# navx_micro_4_1.net
KiCad netlist of a schematic drawn in EAGLE
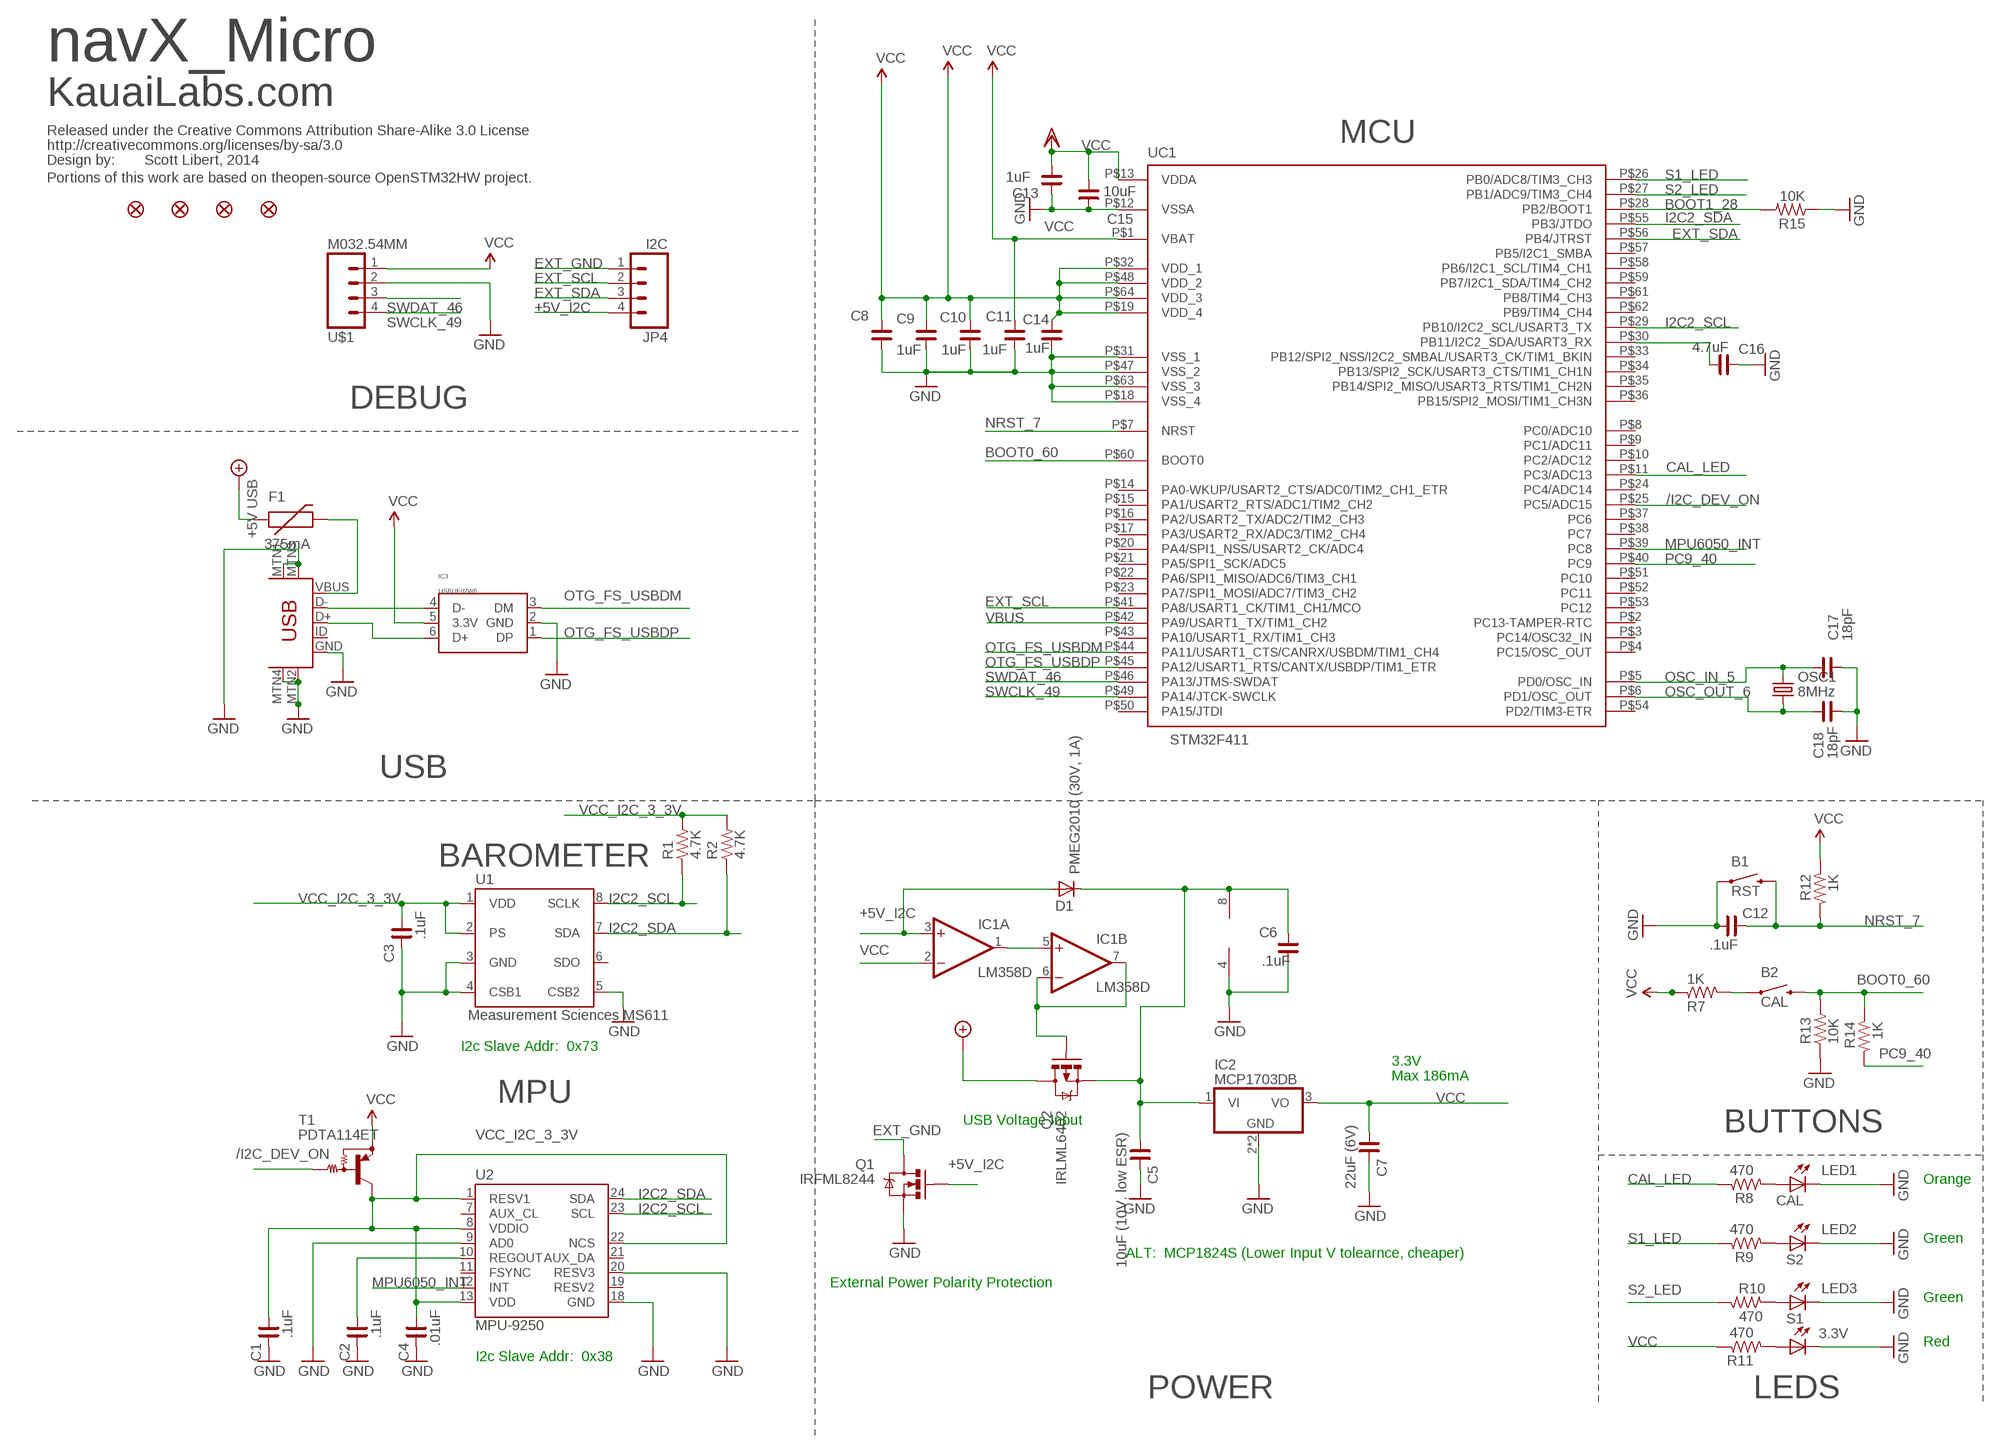
[diagram p0: schematic, sheet 1]

(export (version "E")
  (design (tool "Eeschema 10.0.6"))
  (components
    (comp (ref "B1")
      (value "RST")
      (footprint "eagle-import:TACTILE-SWITCH-1101NE")
      (libsource (lib "eagle-import") (part "SWITCH-MOMENTARY-2-SMD-1101NE"))
    )
    (comp (ref "B2")
      (value "CAL")
      (footprint "eagle-import:TACTILE-SWITCH-1101NE")
      (libsource (lib "eagle-import") (part "SWITCH-MOMENTARY-2-SMD-1101NE"))
    )
    (comp (ref "C1")
      (value ".1uF")
      (footprint "eagle-import:C0603")
      (libsource (lib "eagle-import") (part "C_0603"))
    )
    (comp (ref "C2")
      (value ".1uF")
      (footprint "eagle-import:C0603")
      (libsource (lib "eagle-import") (part "C_0603"))
    )
    (comp (ref "C3")
      (value ".1uF")
      (footprint "eagle-import:C0603")
      (fields (field (name "DIGIKEY_PART_NUMBER") "399-1096-1-ND"))
      (libsource (lib "eagle-import") (part "C_0603"))
    )
    (comp (ref "C4")
      (value ".01uF")
      (footprint "eagle-import:C0603")
      (libsource (lib "eagle-import") (part "C_0603"))
    )
    (comp (ref "C5")
      (value "10uF (10V. low ESR)")
      (footprint "eagle-import:C0805")
      (fields (field (name "DIGIKEY_PART_NUMBER") "399-1158-1-ND"))
      (libsource (lib "eagle-import") (part "C_0805"))
    )
    (comp (ref "C6")
      (value ".1uF")
      (footprint "eagle-import:C0603")
      (libsource (lib "eagle-import") (part "C_0603"))
    )
    (comp (ref "C7")
      (value "22uF (6V)")
      (footprint "eagle-import:C0805")
      (fields (field (name "DIGIKEY_PART_NUMBER") "399-1158-1-ND"))
      (libsource (lib "eagle-import") (part "C_0805"))
    )
    (comp (ref "C8")
      (value "1uF")
      (footprint "eagle-import:C0603")
      (fields (field (name "DIGIKEY_PART_NUMBER") "399-3118-1-ND"))
      (libsource (lib "eagle-import") (part "C_0603"))
    )
    (comp (ref "C9")
      (value "1uF")
      (footprint "eagle-import:C0603")
      (libsource (lib "eagle-import") (part "C_0603"))
    )
    (comp (ref "C10")
      (value "1uF")
      (footprint "eagle-import:C0603")
      (libsource (lib "eagle-import") (part "C_0603"))
    )
    (comp (ref "C11")
      (value "1uF")
      (footprint "eagle-import:C0603")
      (libsource (lib "eagle-import") (part "C_0603"))
    )
    (comp (ref "C12")
      (value ".1uF")
      (footprint "eagle-import:C0603")
      (libsource (lib "eagle-import") (part "C_0603"))
    )
    (comp (ref "C13")
      (value "1uF")
      (footprint "eagle-import:C0603")
      (libsource (lib "eagle-import") (part "C_0603"))
    )
    (comp (ref "C14")
      (value "1uF")
      (footprint "eagle-import:C0603")
      (libsource (lib "eagle-import") (part "C_0603"))
    )
    (comp (ref "C15")
      (value "10uF")
      (footprint "eagle-import:C0805")
      (libsource (lib "eagle-import") (part "C_0805"))
    )
    (comp (ref "C16")
      (value "4.7uF")
      (footprint "eagle-import:C0603")
      (libsource (lib "eagle-import") (part "C_0603"))
    )
    (comp (ref "C17")
      (value "18pF")
      (footprint "eagle-import:C0603")
      (libsource (lib "eagle-import") (part "C_0603"))
    )
    (comp (ref "C18")
      (value "18pF")
      (footprint "eagle-import:C0603")
      (libsource (lib "eagle-import") (part "C_0603"))
    )
    (comp (ref "D1")
      (value "PMEG2010 (30V, 1A)")
      (footprint "eagle-import:SOD-323")
      (libsource (lib "eagle-import") (part "DIODESOD-323"))
    )
    (comp (ref "F1")
      (value "375mA")
      (footprint "eagle-import:0603")
      (libsource (lib "eagle-import") (part "PTC0603"))
    )
    (comp (ref "IC1")
      (value "LM358D")
      (footprint "eagle-import:SO08")
      (libsource (lib "eagle-import") (part "LM358D"))
    )
    (comp (ref "IC2")
      (value "MCP1703DB")
      (footprint "eagle-import:MCP1703DB")
      (fields (field (name "DIGIKEY_PART_NUMBER") "MCP1703T-3302E/DBCT-ND"))
      (libsource (lib "eagle-import") (part "MCP1703DB"))
    )
    (comp (ref "IC3")
      (value "USBUF02W6")
      (footprint "eagle-import:SC70-6")
      (fields (field (name "DIGIKEY_PART_NUMBER") "497-3743-1-ND"))
      (libsource (lib "eagle-import") (part "USBUF02W6"))
    )
    (comp (ref "JP4")
      (value "I2C")
      (footprint "eagle-import:1X04")
      (libsource (lib "eagle-import") (part "M04PTH"))
    )
    (comp (ref "JP21")
      (value "FIDUCIAL1X2")
      (footprint "eagle-import:FIDUCIAL-1X2")
      (libsource (lib "eagle-import") (part "FIDUCIAL1X2"))
    )
    (comp (ref "JP22")
      (value "FIDUCIAL1X2")
      (footprint "eagle-import:FIDUCIAL-1X2")
      (libsource (lib "eagle-import") (part "FIDUCIAL1X2"))
    )
    (comp (ref "JP23")
      (value "FIDUCIAL1X2")
      (footprint "eagle-import:FIDUCIAL-1X2")
      (libsource (lib "eagle-import") (part "FIDUCIAL1X2"))
    )
    (comp (ref "JP24")
      (value "FIDUCIAL1X2")
      (footprint "eagle-import:FIDUCIAL-1X2")
      (libsource (lib "eagle-import") (part "FIDUCIAL1X2"))
    )
    (comp (ref "LED1")
      (value "CAL")
      (footprint "eagle-import:CHIP-LED0603")
      (libsource (lib "eagle-import") (part "LEDCHIP-LED0603"))
    )
    (comp (ref "LED2")
      (value "S2")
      (footprint "eagle-import:CHIP-LED0603")
      (libsource (lib "eagle-import") (part "LEDCHIP-LED0603"))
    )
    (comp (ref "LED3")
      (value "S1")
      (footprint "eagle-import:CHIP-LED0603")
      (libsource (lib "eagle-import") (part "LEDCHIP-LED0603"))
    )
    (comp (ref "LED4")
      (value "3.3V")
      (footprint "eagle-import:CHIP-LED0603")
      (libsource (lib "eagle-import") (part "LEDCHIP-LED0603"))
    )
    (comp (ref "LICENSE_TEXT")
      (value "CREATIVE_COMMONS")
      (footprint "eagle-import:CREATIVE_COMMONS")
      (libsource (lib "eagle-import") (part "CREATIVE_COMMONS"))
    )
    (comp (ref "OSC1")
      (value "8MHz")
      (footprint "eagle-import:CRYSTAL-SMD-5X3")
      (libsource (lib "eagle-import") (part "CRYSTAL5X3"))
    )
    (comp (ref "Q1")
      (value "IRFML8244")
      (footprint "eagle-import:SOT23")
      (fields (field (name "DIGIKEY_PART_NUMBER") "DMN3404LDICT-ND"))
      (libsource (lib "eagle-import") (part "MOSFET-NCHANNELBSS123LT1G"))
    )
    (comp (ref "Q2")
      (value "IRLML6402")
      (footprint "eagle-import:SOT23-3")
      (libsource (lib "eagle-import") (part "MOSFET-PCHANNELSMD"))
    )
    (comp (ref "R1")
      (value "4.7K")
      (footprint "eagle-import:R0603")
      (libsource (lib "eagle-import") (part "R_0603"))
    )
    (comp (ref "R2")
      (value "4.7K")
      (footprint "eagle-import:R0603")
      (libsource (lib "eagle-import") (part "R_0603"))
    )
    (comp (ref "R7")
      (value "1K")
      (footprint "eagle-import:R0603")
      (libsource (lib "eagle-import") (part "R_0603"))
    )
    (comp (ref "R8")
      (value "470")
      (footprint "eagle-import:R0603")
      (libsource (lib "eagle-import") (part "R_0603"))
    )
    (comp (ref "R9")
      (value "470")
      (footprint "eagle-import:R0603")
      (libsource (lib "eagle-import") (part "R_0603"))
    )
    (comp (ref "R10")
      (value "470")
      (footprint "eagle-import:R0603")
      (libsource (lib "eagle-import") (part "R_0603"))
    )
    (comp (ref "R11")
      (value "470")
      (footprint "eagle-import:R0603")
      (libsource (lib "eagle-import") (part "R_0603"))
    )
    (comp (ref "R12")
      (value "1K")
      (footprint "eagle-import:R0603")
      (libsource (lib "eagle-import") (part "R_0603"))
    )
    (comp (ref "R13")
      (value "10K")
      (footprint "eagle-import:R0603")
      (libsource (lib "eagle-import") (part "R_0603"))
    )
    (comp (ref "R14")
      (value "1K")
      (footprint "eagle-import:R0603")
      (libsource (lib "eagle-import") (part "R_0603"))
    )
    (comp (ref "R15")
      (value "10K")
      (footprint "eagle-import:R0603")
      (libsource (lib "eagle-import") (part "R_0603"))
    )
    (comp (ref "T1")
      (value "PDTA114ET")
      (footprint "eagle-import:SOT23-3")
      (libsource (lib "eagle-import") (part "PNP-DRIVERSOT23-3"))
    )
    (comp (ref "U$1")
      (value "M032.54MM")
      (footprint "eagle-import:1X04_NO_SILK")
      (libsource (lib "eagle-import") (part "M041X04_NO_SILK"))
    )
    (comp (ref "U1")
      (value "Measurement Sciences MS611")
      (footprint "eagle-import:MS5611")
      (fields (field (name "DIGIKEY_PART_NUMBER") "MPL115A2-ND"))
      (libsource (lib "eagle-import") (part "MS5611"))
    )
    (comp (ref "U2")
      (value "MPU-9250")
      (footprint "eagle-import:QFN24_3MM_INVENSENSE")
      (fields
        (field (name "DIGIKEY_PART_NUMBER") "1428-1019-1-ND")
        (field (name "MANUFACTURER") "INVENSENSE")
      )
      (libsource (lib "eagle-import") (part "MPU-9250"))
    )
    (comp (ref "UC1")
      (value "STM32F411")
      (footprint "eagle-import:TQFP-10X10-64")
      (fields (field (name "DIGIKEY_PART_NUMBER") "497-11154-ND"))
      (libsource (lib "eagle-import") (part "STM32F103"))
    )
    (comp (ref "USB")
      (value "Mini-USB")
      (footprint "eagle-import:USB-MINIB")
      (fields (field (name "DIGIKEY_PART_NUMBER") "151-1206-1-ND"))
      (libsource (lib "eagle-import") (part "USB-MINIB-5PIN"))
    )
  )
  (nets
    (net (code "1") (name "+5V USB") (class "Default")
      (node (ref "F1") (pin "1") (pinfunction "1_1") (pintype "bidirectional"))
      (node (ref "Q2") (pin "3") (pinfunction "D_3") (pintype "passive"))
    )
    (net (code "2") (name "/+5V_I2C") (class "Default")
      (node (ref "D1") (pin "A") (pinfunction "A_A") (pintype "passive"))
      (node (ref "IC1") (pin "3") (pinfunction "+IN_3") (pintype "input"))
      (node (ref "JP4") (pin "4") (pinfunction "4_4") (pintype "passive"))
      (node (ref "Q1") (pin "1") (pinfunction "G_1") (pintype "passive"))
    )
    (net (code "3") (name "/BOOT0_60") (class "Default")
      (node (ref "B2") (pin "P$2") (pinfunction "2_P$2") (pintype "passive"))
      (node (ref "R13") (pin "2") (pinfunction "2_2") (pintype "passive"))
      (node (ref "R14") (pin "1") (pinfunction "1_1") (pintype "passive"))
      (node (ref "UC1") (pin "P$60") (pinfunction "BOOT0_P$60") (pintype "bidirectional"))
    )
    (net (code "4") (name "/BOOT1_28") (class "Default")
      (node (ref "R15") (pin "2") (pinfunction "2_2") (pintype "passive"))
      (node (ref "UC1") (pin "P$28") (pinfunction "PB2/BOOT1_P$28") (pintype "bidirectional"))
    )
    (net (code "5") (name "/CAL_LED") (class "Default")
      (node (ref "R8") (pin "1") (pinfunction "1_1") (pintype "passive"))
      (node (ref "UC1") (pin "P$11") (pinfunction "PC3/ADC13_P$11") (pintype "bidirectional"))
    )
    (net (code "6") (name "/EXT_GND") (class "Default")
      (node (ref "JP4") (pin "1") (pinfunction "1_1") (pintype "passive"))
      (node (ref "Q1") (pin "3") (pinfunction "D_3") (pintype "passive"))
    )
    (net (code "7") (name "/EXT_SCL") (class "Default")
      (node (ref "JP4") (pin "2") (pinfunction "2_2") (pintype "passive"))
      (node (ref "UC1") (pin "P$41") (pinfunction "PA8/USART1_CK/TIM1_CH1/MCO_P$41") (pintype "bidirectional"))
    )
    (net (code "8") (name "/EXT_SDA") (class "Default")
      (node (ref "JP4") (pin "3") (pinfunction "3_3") (pintype "passive"))
      (node (ref "UC1") (pin "P$56") (pinfunction "PB4/JTRST_P$56") (pintype "bidirectional"))
    )
    (net (code "9") (name "/I2C2_SCL") (class "Default")
      (node (ref "R1") (pin "1") (pinfunction "1_1") (pintype "passive"))
      (node (ref "U1") (pin "8") (pinfunction "SCLK_8") (pintype "bidirectional"))
      (node (ref "U2") (pin "23") (pinfunction "SCL_23") (pintype "bidirectional"))
      (node (ref "UC1") (pin "P$29") (pinfunction "PB10/I2C2_SCL/USART3_TX_P$29") (pintype "bidirectional"))
    )
    (net (code "10") (name "/I2C2_SDA") (class "Default")
      (node (ref "R2") (pin "1") (pinfunction "1_1") (pintype "passive"))
      (node (ref "U1") (pin "7") (pinfunction "SDA_7") (pintype "bidirectional"))
      (node (ref "U2") (pin "24") (pinfunction "SDA_24") (pintype "bidirectional"))
      (node (ref "UC1") (pin "P$55") (pinfunction "PB3/JTDO_P$55") (pintype "bidirectional"))
    )
    (net (code "11") (name "/MPU6050_INT") (class "Default")
      (node (ref "U2") (pin "12") (pinfunction "INT_12") (pintype "bidirectional"))
      (node (ref "UC1") (pin "P$39") (pinfunction "PC8_P$39") (pintype "bidirectional"))
    )
    (net (code "12") (name "/NRST_7") (class "Default")
      (node (ref "B1") (pin "P$2") (pinfunction "2_P$2") (pintype "passive"))
      (node (ref "C12") (pin "2") (pinfunction "2_2") (pintype "passive"))
      (node (ref "R12") (pin "2") (pinfunction "2_2") (pintype "passive"))
      (node (ref "UC1") (pin "P$7") (pinfunction "NRST_P$7") (pintype "bidirectional"))
    )
    (net (code "13") (name "/OSC_IN_5") (class "Default")
      (node (ref "C17") (pin "2") (pinfunction "2_2") (pintype "passive"))
      (node (ref "OSC1") (pin "3") (pinfunction "2_3") (pintype "passive"))
      (node (ref "UC1") (pin "P$5") (pinfunction "PD0/OSC_IN_P$5") (pintype "bidirectional"))
    )
    (net (code "14") (name "/OSC_OUT_6") (class "Default")
      (node (ref "C18") (pin "2") (pinfunction "2_2") (pintype "passive"))
      (node (ref "OSC1") (pin "1") (pinfunction "1_1") (pintype "passive"))
      (node (ref "UC1") (pin "P$6") (pinfunction "PD1/OSC_OUT_P$6") (pintype "bidirectional"))
    )
    (net (code "15") (name "/OTG_FS_USBDM") (class "Default")
      (node (ref "IC3") (pin "3") (pinfunction "DM_3") (pintype "bidirectional"))
      (node (ref "UC1") (pin "P$44") (pinfunction "PA11/USART1_CTS/CANRX/USBDM/TIM1_CH4_P$44") (pintype "bidirectional"))
    )
    (net (code "16") (name "/OTG_FS_USBDP") (class "Default")
      (node (ref "IC3") (pin "1") (pinfunction "DP_1") (pintype "bidirectional"))
      (node (ref "UC1") (pin "P$45") (pinfunction "PA12/USART1_RTS/CANTX/USBDP/TIM1_ETR_P$45") (pintype "bidirectional"))
    )
    (net (code "17") (name "/PC9_40") (class "Default")
      (node (ref "R14") (pin "2") (pinfunction "2_2") (pintype "passive"))
      (node (ref "UC1") (pin "P$40") (pinfunction "PC9_P$40") (pintype "bidirectional"))
    )
    (net (code "18") (name "/S1_LED") (class "Default")
      (node (ref "R9") (pin "1") (pinfunction "1_1") (pintype "passive"))
      (node (ref "UC1") (pin "P$26") (pinfunction "PB0/ADC8/TIM3_CH3_P$26") (pintype "bidirectional"))
    )
    (net (code "19") (name "/S2_LED") (class "Default")
      (node (ref "R10") (pin "2") (pinfunction "2_2") (pintype "passive"))
      (node (ref "UC1") (pin "P$27") (pinfunction "PB1/ADC9/TIM3_CH4_P$27") (pintype "bidirectional"))
    )
    (net (code "20") (name "/SWCLK_49") (class "Default")
      (node (ref "U$1") (pin "4") (pinfunction "4_4") (pintype "passive"))
      (node (ref "UC1") (pin "P$49") (pinfunction "PA14/JTCK-SWCLK_P$49") (pintype "bidirectional"))
    )
    (net (code "21") (name "/SWDAT_46") (class "Default")
      (node (ref "U$1") (pin "3") (pinfunction "3_3") (pintype "passive"))
      (node (ref "UC1") (pin "P$46") (pinfunction "PA13/JTMS-SWDAT_P$46") (pintype "bidirectional"))
    )
    (net (code "22") (name "/VBUS") (class "Default")
      (node (ref "F1") (pin "2") (pinfunction "2_2") (pintype "bidirectional"))
      (node (ref "UC1") (pin "P$42") (pinfunction "PA9/USART1_TX/TIM1_CH2_P$42") (pintype "bidirectional"))
      (node (ref "USB") (pin "VBUS") (pinfunction "VBUS_VBUS") (pintype "bidirectional"))
    )
    (net (code "23") (name "/VCC_I2C_3_3V") (class "Default")
      (node (ref "C1") (pin "1") (pinfunction "1_1") (pintype "passive"))
      (node (ref "C3") (pin "1") (pinfunction "1_1") (pintype "passive"))
      (node (ref "C4") (pin "1") (pinfunction "1_1") (pintype "passive"))
      (node (ref "R1") (pin "2") (pinfunction "2_2") (pintype "passive"))
      (node (ref "R2") (pin "2") (pinfunction "2_2") (pintype "passive"))
      (node (ref "T1") (pin "3") (pinfunction "C_3") (pintype "passive"))
      (node (ref "U1") (pin "1") (pinfunction "VDD_1") (pintype "bidirectional"))
      (node (ref "U1") (pin "2") (pinfunction "PS_2") (pintype "bidirectional"))
      (node (ref "U2") (pin "1") (pinfunction "RESV1_1") (pintype "bidirectional"))
      (node (ref "U2") (pin "13") (pinfunction "VDD_13") (pintype "bidirectional"))
      (node (ref "U2") (pin "22") (pinfunction "NCS_22") (pintype "bidirectional"))
      (node (ref "U2") (pin "8") (pinfunction "VDDIO_8") (pintype "bidirectional"))
    )
    (net (code "24") (name "/{slash}I2C_DEV_ON") (class "Default")
      (node (ref "T1") (pin "1") (pinfunction "B_1") (pintype "passive"))
      (node (ref "UC1") (pin "P$25") (pinfunction "PC5/ADC15_P$25") (pintype "bidirectional"))
    )
    (net (code "25") (name "GND") (class "Default")
      (node (ref "B1") (pin "P$1") (pinfunction "1_P$1") (pintype "passive"))
      (node (ref "C1") (pin "2") (pinfunction "2_2") (pintype "passive"))
      (node (ref "C10") (pin "1") (pinfunction "1_1") (pintype "passive"))
      (node (ref "C11") (pin "1") (pinfunction "1_1") (pintype "passive"))
      (node (ref "C12") (pin "1") (pinfunction "1_1") (pintype "passive"))
      (node (ref "C13") (pin "1") (pinfunction "1_1") (pintype "passive"))
      (node (ref "C14") (pin "1") (pinfunction "1_1") (pintype "passive"))
      (node (ref "C15") (pin "2") (pinfunction "2_2") (pintype "passive"))
      (node (ref "C16") (pin "1") (pinfunction "1_1") (pintype "passive"))
      (node (ref "C17") (pin "1") (pinfunction "1_1") (pintype "passive"))
      (node (ref "C18") (pin "1") (pinfunction "1_1") (pintype "passive"))
      (node (ref "C2") (pin "2") (pinfunction "2_2") (pintype "passive"))
      (node (ref "C3") (pin "2") (pinfunction "2_2") (pintype "passive"))
      (node (ref "C4") (pin "2") (pinfunction "2_2") (pintype "passive"))
      (node (ref "C5") (pin "2") (pinfunction "2_2") (pintype "passive"))
      (node (ref "C6") (pin "1") (pinfunction "1_1") (pintype "passive"))
      (node (ref "C7") (pin "2") (pinfunction "2_2") (pintype "passive"))
      (node (ref "C8") (pin "1") (pinfunction "1_1") (pintype "passive"))
      (node (ref "C9") (pin "1") (pinfunction "1_1") (pintype "passive"))
      (node (ref "IC1") (pin "4") (pinfunction "V-_4") (pintype "power_in"))
      (node (ref "IC2") (pin "2") (pinfunction "GND_2") (pintype "passive"))
      (node (ref "IC2") (pin "4") (pinfunction "GND_4") (pintype "passive"))
      (node (ref "IC3") (pin "2") (pinfunction "GND_2") (pintype "bidirectional"))
      (node (ref "LED1") (pin "C") (pinfunction "C_C") (pintype "passive"))
      (node (ref "LED2") (pin "C") (pinfunction "C_C") (pintype "passive"))
      (node (ref "LED3") (pin "C") (pinfunction "C_C") (pintype "passive"))
      (node (ref "LED4") (pin "C") (pinfunction "C_C") (pintype "passive"))
      (node (ref "Q1") (pin "2") (pinfunction "S_2") (pintype "passive"))
      (node (ref "R13") (pin "1") (pinfunction "1_1") (pintype "passive"))
      (node (ref "R15") (pin "1") (pinfunction "1_1") (pintype "passive"))
      (node (ref "U$1") (pin "2") (pinfunction "2_2") (pintype "passive"))
      (node (ref "U1") (pin "3") (pinfunction "GND_3") (pintype "bidirectional"))
      (node (ref "U1") (pin "4") (pinfunction "CSB1_4") (pintype "bidirectional"))
      (node (ref "U1") (pin "5") (pinfunction "CSB2_5") (pintype "bidirectional"))
      (node (ref "U2") (pin "18") (pinfunction "GND_18") (pintype "bidirectional"))
      (node (ref "U2") (pin "20") (pinfunction "RESV3_20") (pintype "bidirectional"))
      (node (ref "U2") (pin "9") (pinfunction "AD0_9") (pintype "bidirectional"))
      (node (ref "UC1") (pin "P$12") (pinfunction "VSSA_P$12") (pintype "power_in"))
      (node (ref "UC1") (pin "P$18") (pinfunction "VSS_4_P$18") (pintype "power_in"))
      (node (ref "UC1") (pin "P$31") (pinfunction "VSS_1_P$31") (pintype "power_in"))
      (node (ref "UC1") (pin "P$47") (pinfunction "VSS_2_P$47") (pintype "power_in"))
      (node (ref "UC1") (pin "P$63") (pinfunction "VSS_3_P$63") (pintype "power_in"))
      (node (ref "USB") (pin "GND") (pinfunction "GND_GND") (pintype "bidirectional"))
      (node (ref "USB") (pin "MTN1") (pinfunction "MTN2_MTN1") (pintype "bidirectional"))
      (node (ref "USB") (pin "MTN2") (pinfunction "MTN3_MTN2") (pintype "bidirectional"))
      (node (ref "USB") (pin "MTN3") (pinfunction "MTN1_MTN3") (pintype "bidirectional"))
      (node (ref "USB") (pin "MTN4") (pinfunction "MTN4_MTN4") (pintype "bidirectional"))
    )
    (net (code "26") (name "Net-(B2-1)") (class "Default")
      (node (ref "B2") (pin "P$1") (pinfunction "1_P$1") (pintype "passive"))
      (node (ref "R7") (pin "2") (pinfunction "2_2") (pintype "passive"))
    )
    (net (code "27") (name "Net-(IC1A-OUT)") (class "Default")
      (node (ref "IC1") (pin "1") (pinfunction "OUT_1") (pintype "output"))
      (node (ref "IC1") (pin "5") (pinfunction "+IN_5") (pintype "input"))
    )
    (net (code "28") (name "Net-(IC1B--IN)") (class "Default")
      (node (ref "IC1") (pin "6") (pinfunction "-IN_6") (pintype "input"))
      (node (ref "IC1") (pin "7") (pinfunction "OUT_7") (pintype "output"))
      (node (ref "Q2") (pin "1") (pinfunction "G_1") (pintype "passive"))
    )
    (net (code "29") (name "Net-(IC1C-V+)") (class "Default")
      (node (ref "C5") (pin "1") (pinfunction "1_1") (pintype "passive"))
      (node (ref "C6") (pin "2") (pinfunction "2_2") (pintype "passive"))
      (node (ref "D1") (pin "C") (pinfunction "C_C") (pintype "passive"))
      (node (ref "IC1") (pin "8") (pinfunction "V+_8") (pintype "power_in"))
      (node (ref "IC2") (pin "1") (pinfunction "VI_1") (pintype "input"))
      (node (ref "Q2") (pin "2") (pinfunction "S_2") (pintype "passive"))
    )
    (net (code "30") (name "Net-(IC3-D+)") (class "Default")
      (node (ref "IC3") (pin "6") (pinfunction "D+_6") (pintype "bidirectional"))
      (node (ref "USB") (pin "D+") (pinfunction "D+_D+") (pintype "bidirectional"))
    )
    (net (code "31") (name "Net-(IC3-D-)") (class "Default")
      (node (ref "IC3") (pin "4") (pinfunction "D-_4") (pintype "bidirectional"))
      (node (ref "USB") (pin "D-") (pinfunction "D-_D-") (pintype "bidirectional"))
    )
    (net (code "32") (name "Net-(LED1-PadA)") (class "Default")
      (node (ref "LED1") (pin "A") (pinfunction "A_A") (pintype "passive"))
      (node (ref "R8") (pin "2") (pinfunction "2_2") (pintype "passive"))
    )
    (net (code "33") (name "Net-(LED2-PadA)") (class "Default")
      (node (ref "LED2") (pin "A") (pinfunction "A_A") (pintype "passive"))
      (node (ref "R9") (pin "2") (pinfunction "2_2") (pintype "passive"))
    )
    (net (code "34") (name "Net-(LED3-PadA)") (class "Default")
      (node (ref "LED3") (pin "A") (pinfunction "A_A") (pintype "passive"))
      (node (ref "R10") (pin "1") (pinfunction "1_1") (pintype "passive"))
    )
    (net (code "35") (name "Net-(LED4-PadA)") (class "Default")
      (node (ref "LED4") (pin "A") (pinfunction "A_A") (pintype "passive"))
      (node (ref "R11") (pin "2") (pinfunction "2_2") (pintype "passive"))
    )
    (net (code "36") (name "Net-(U2-REGOUT)") (class "Default")
      (node (ref "C2") (pin "1") (pinfunction "1_1") (pintype "passive"))
      (node (ref "U2") (pin "10") (pinfunction "REGOUT_10") (pintype "bidirectional"))
    )
    (net (code "37") (name "Net-(UC1-PB11{slash}I2C2_SDA{slash}USART3_RX)") (class "Default")
      (node (ref "C16") (pin "2") (pinfunction "2_2") (pintype "passive"))
      (node (ref "UC1") (pin "P$30") (pinfunction "PB11/I2C2_SDA/USART3_RX_P$30") (pintype "bidirectional"))
    )
    (net (code "38") (name "VCC") (class "Default")
      (node (ref "C10") (pin "2") (pinfunction "2_2") (pintype "passive"))
      (node (ref "C11") (pin "2") (pinfunction "2_2") (pintype "passive"))
      (node (ref "C13") (pin "2") (pinfunction "2_2") (pintype "passive"))
      (node (ref "C14") (pin "2") (pinfunction "2_2") (pintype "passive"))
      (node (ref "C15") (pin "1") (pinfunction "1_1") (pintype "passive"))
      (node (ref "C7") (pin "1") (pinfunction "1_1") (pintype "passive"))
      (node (ref "C8") (pin "2") (pinfunction "2_2") (pintype "passive"))
      (node (ref "C9") (pin "2") (pinfunction "2_2") (pintype "passive"))
      (node (ref "IC1") (pin "2") (pinfunction "-IN_2") (pintype "input"))
      (node (ref "IC2") (pin "3") (pinfunction "VO_3") (pintype "passive"))
      (node (ref "IC3") (pin "5") (pinfunction "3.3V_5") (pintype "bidirectional"))
      (node (ref "R11") (pin "1") (pinfunction "1_1") (pintype "passive"))
      (node (ref "R12") (pin "1") (pinfunction "1_1") (pintype "passive"))
      (node (ref "R7") (pin "1") (pinfunction "1_1") (pintype "passive"))
      (node (ref "T1") (pin "2") (pinfunction "E_2") (pintype "passive"))
      (node (ref "U$1") (pin "1") (pinfunction "1_1") (pintype "passive"))
      (node (ref "UC1") (pin "P$1") (pinfunction "VBAT_P$1") (pintype "power_in"))
      (node (ref "UC1") (pin "P$13") (pinfunction "VDDA_P$13") (pintype "power_in"))
      (node (ref "UC1") (pin "P$19") (pinfunction "VDD_4_P$19") (pintype "power_in"))
      (node (ref "UC1") (pin "P$32") (pinfunction "VDD_1_P$32") (pintype "power_in"))
      (node (ref "UC1") (pin "P$48") (pinfunction "VDD_2_P$48") (pintype "power_in"))
      (node (ref "UC1") (pin "P$64") (pinfunction "VDD_3_P$64") (pintype "power_in"))
    )
    (net (code "39") (name "unconnected-(U1-SDO-Pad6)") (class "Default")
      (node (ref "U1") (pin "6") (pinfunction "SDO_6") (pintype "bidirectional"))
    )
    (net (code "40") (name "unconnected-(U2-AUX_CL-Pad7)") (class "Default")
      (node (ref "U2") (pin "7") (pinfunction "AUX_CL_7") (pintype "bidirectional"))
    )
    (net (code "41") (name "unconnected-(U2-AUX_DA-Pad21)") (class "Default")
      (node (ref "U2") (pin "21") (pinfunction "AUX_DA_21") (pintype "bidirectional"))
    )
    (net (code "42") (name "unconnected-(U2-FSYNC-Pad11)") (class "Default")
      (node (ref "U2") (pin "11") (pinfunction "FSYNC_11") (pintype "bidirectional"))
    )
    (net (code "43") (name "unconnected-(U2-RESV2-Pad19)") (class "Default")
      (node (ref "U2") (pin "19") (pinfunction "RESV2_19") (pintype "bidirectional"))
    )
    (net (code "44") (name "unconnected-(UC1-PA0-WKUP{slash}USART2_CTS{slash}ADC0{slash}TIM2_CH1_ETR-PadP$14)") (class "Default")
      (node (ref "UC1") (pin "P$14") (pinfunction "PA0-WKUP/USART2_CTS/ADC0/TIM2_CH1_ETR_P$14") (pintype "bidirectional"))
    )
    (net (code "45") (name "unconnected-(UC1-PA1{slash}USART2_RTS{slash}ADC1{slash}TIM2_CH2-PadP$15)") (class "Default")
      (node (ref "UC1") (pin "P$15") (pinfunction "PA1/USART2_RTS/ADC1/TIM2_CH2_P$15") (pintype "bidirectional"))
    )
    (net (code "46") (name "unconnected-(UC1-PA2{slash}USART2_TX{slash}ADC2{slash}TIM2_CH3-PadP$16)") (class "Default")
      (node (ref "UC1") (pin "P$16") (pinfunction "PA2/USART2_TX/ADC2/TIM2_CH3_P$16") (pintype "bidirectional"))
    )
    (net (code "47") (name "unconnected-(UC1-PA3{slash}USART2_RX{slash}ADC3{slash}TIM2_CH4-PadP$17)") (class "Default")
      (node (ref "UC1") (pin "P$17") (pinfunction "PA3/USART2_RX/ADC3/TIM2_CH4_P$17") (pintype "bidirectional"))
    )
    (net (code "48") (name "unconnected-(UC1-PA4{slash}SPI1_NSS{slash}USART2_CK{slash}ADC4-PadP$20)") (class "Default")
      (node (ref "UC1") (pin "P$20") (pinfunction "PA4/SPI1_NSS/USART2_CK/ADC4_P$20") (pintype "bidirectional"))
    )
    (net (code "49") (name "unconnected-(UC1-PA5{slash}SPI1_SCK{slash}ADC5-PadP$21)") (class "Default")
      (node (ref "UC1") (pin "P$21") (pinfunction "PA5/SPI1_SCK/ADC5_P$21") (pintype "bidirectional"))
    )
    (net (code "50") (name "unconnected-(UC1-PA6{slash}SPI1_MISO{slash}ADC6{slash}TIM3_CH1-PadP$22)") (class "Default")
      (node (ref "UC1") (pin "P$22") (pinfunction "PA6/SPI1_MISO/ADC6/TIM3_CH1_P$22") (pintype "bidirectional"))
    )
    (net (code "51") (name "unconnected-(UC1-PA7{slash}SPI1_MOSI{slash}ADC7{slash}TIM3_CH2-PadP$23)") (class "Default")
      (node (ref "UC1") (pin "P$23") (pinfunction "PA7/SPI1_MOSI/ADC7/TIM3_CH2_P$23") (pintype "bidirectional"))
    )
    (net (code "52") (name "unconnected-(UC1-PA10{slash}USART1_RX{slash}TIM1_CH3-PadP$43)") (class "Default")
      (node (ref "UC1") (pin "P$43") (pinfunction "PA10/USART1_RX/TIM1_CH3_P$43") (pintype "bidirectional"))
    )
    (net (code "53") (name "unconnected-(UC1-PA15{slash}JTDI-PadP$50)") (class "Default")
      (node (ref "UC1") (pin "P$50") (pinfunction "PA15/JTDI_P$50") (pintype "bidirectional"))
    )
    (net (code "54") (name "unconnected-(UC1-PB5{slash}I2C1_SMBA-PadP$57)") (class "Default")
      (node (ref "UC1") (pin "P$57") (pinfunction "PB5/I2C1_SMBA_P$57") (pintype "bidirectional"))
    )
    (net (code "55") (name "unconnected-(UC1-PB6{slash}I2C1_SCL{slash}TIM4_CH1-PadP$58)") (class "Default")
      (node (ref "UC1") (pin "P$58") (pinfunction "PB6/I2C1_SCL/TIM4_CH1_P$58") (pintype "bidirectional"))
    )
    (net (code "56") (name "unconnected-(UC1-PB7{slash}I2C1_SDA{slash}TIM4_CH2-PadP$59)") (class "Default")
      (node (ref "UC1") (pin "P$59") (pinfunction "PB7/I2C1_SDA/TIM4_CH2_P$59") (pintype "bidirectional"))
    )
    (net (code "57") (name "unconnected-(UC1-PB8{slash}TIM4_CH3-PadP$61)") (class "Default")
      (node (ref "UC1") (pin "P$61") (pinfunction "PB8/TIM4_CH3_P$61") (pintype "bidirectional"))
    )
    (net (code "58") (name "unconnected-(UC1-PB9{slash}TIM4_CH4-PadP$62)") (class "Default")
      (node (ref "UC1") (pin "P$62") (pinfunction "PB9/TIM4_CH4_P$62") (pintype "bidirectional"))
    )
    (net (code "59") (name "unconnected-(UC1-PB12{slash}SPI2_NSS{slash}I2C2_SMBAL{slash}USART3_CK{slash}TIM1_BKIN-PadP$33)") (class "Default")
      (node (ref "UC1") (pin "P$33") (pinfunction "PB12/SPI2_NSS/I2C2_SMBAL/USART3_CK/TIM1_BKIN_P$33") (pintype "bidirectional"))
    )
    (net (code "60") (name "unconnected-(UC1-PB13{slash}SPI2_SCK{slash}USART3_CTS{slash}TIM1_CH1N-PadP$34)") (class "Default")
      (node (ref "UC1") (pin "P$34") (pinfunction "PB13/SPI2_SCK/USART3_CTS/TIM1_CH1N_P$34") (pintype "bidirectional"))
    )
    (net (code "61") (name "unconnected-(UC1-PB14{slash}SPI2_MISO{slash}USART3_RTS{slash}TIM1_CH2N-PadP$35)") (class "Default")
      (node (ref "UC1") (pin "P$35") (pinfunction "PB14/SPI2_MISO/USART3_RTS/TIM1_CH2N_P$35") (pintype "bidirectional"))
    )
    (net (code "62") (name "unconnected-(UC1-PB15{slash}SPI2_MOSI{slash}TIM1_CH3N-PadP$36)") (class "Default")
      (node (ref "UC1") (pin "P$36") (pinfunction "PB15/SPI2_MOSI/TIM1_CH3N_P$36") (pintype "bidirectional"))
    )
    (net (code "63") (name "unconnected-(UC1-PC0{slash}ADC10-PadP$8)") (class "Default")
      (node (ref "UC1") (pin "P$8") (pinfunction "PC0/ADC10_P$8") (pintype "bidirectional"))
    )
    (net (code "64") (name "unconnected-(UC1-PC1{slash}ADC11-PadP$9)") (class "Default")
      (node (ref "UC1") (pin "P$9") (pinfunction "PC1/ADC11_P$9") (pintype "bidirectional"))
    )
    (net (code "65") (name "unconnected-(UC1-PC2{slash}ADC12-PadP$10)") (class "Default")
      (node (ref "UC1") (pin "P$10") (pinfunction "PC2/ADC12_P$10") (pintype "bidirectional"))
    )
    (net (code "66") (name "unconnected-(UC1-PC4{slash}ADC14-PadP$24)") (class "Default")
      (node (ref "UC1") (pin "P$24") (pinfunction "PC4/ADC14_P$24") (pintype "bidirectional"))
    )
    (net (code "67") (name "unconnected-(UC1-PC6-PadP$37)") (class "Default")
      (node (ref "UC1") (pin "P$37") (pinfunction "PC6_P$37") (pintype "bidirectional"))
    )
    (net (code "68") (name "unconnected-(UC1-PC7-PadP$38)") (class "Default")
      (node (ref "UC1") (pin "P$38") (pinfunction "PC7_P$38") (pintype "bidirectional"))
    )
    (net (code "69") (name "unconnected-(UC1-PC10-PadP$51)") (class "Default")
      (node (ref "UC1") (pin "P$51") (pinfunction "PC10_P$51") (pintype "bidirectional"))
    )
    (net (code "70") (name "unconnected-(UC1-PC11-PadP$52)") (class "Default")
      (node (ref "UC1") (pin "P$52") (pinfunction "PC11_P$52") (pintype "bidirectional"))
    )
    (net (code "71") (name "unconnected-(UC1-PC12-PadP$53)") (class "Default")
      (node (ref "UC1") (pin "P$53") (pinfunction "PC12_P$53") (pintype "bidirectional"))
    )
    (net (code "72") (name "unconnected-(UC1-PC13-TAMPER-RTC-PadP$2)") (class "Default")
      (node (ref "UC1") (pin "P$2") (pinfunction "PC13-TAMPER-RTC_P$2") (pintype "bidirectional"))
    )
    (net (code "73") (name "unconnected-(UC1-PC14{slash}OSC32_IN-PadP$3)") (class "Default")
      (node (ref "UC1") (pin "P$3") (pinfunction "PC14/OSC32_IN_P$3") (pintype "bidirectional"))
    )
    (net (code "74") (name "unconnected-(UC1-PC15{slash}OSC_OUT-PadP$4)") (class "Default")
      (node (ref "UC1") (pin "P$4") (pinfunction "PC15/OSC_OUT_P$4") (pintype "bidirectional"))
    )
    (net (code "75") (name "unconnected-(UC1-PD2{slash}TIM3-ETR-PadP$54)") (class "Default")
      (node (ref "UC1") (pin "P$54") (pinfunction "PD2/TIM3-ETR_P$54") (pintype "bidirectional"))
    )
    (net (code "76") (name "unconnected-(USB-PadID)") (class "Default")
      (node (ref "USB") (pin "ID") (pinfunction "ID_ID") (pintype "bidirectional"))
    )
  )
)
